# Sound_pollution.net
KiCad netlist of a schematic drawn in EAGLE
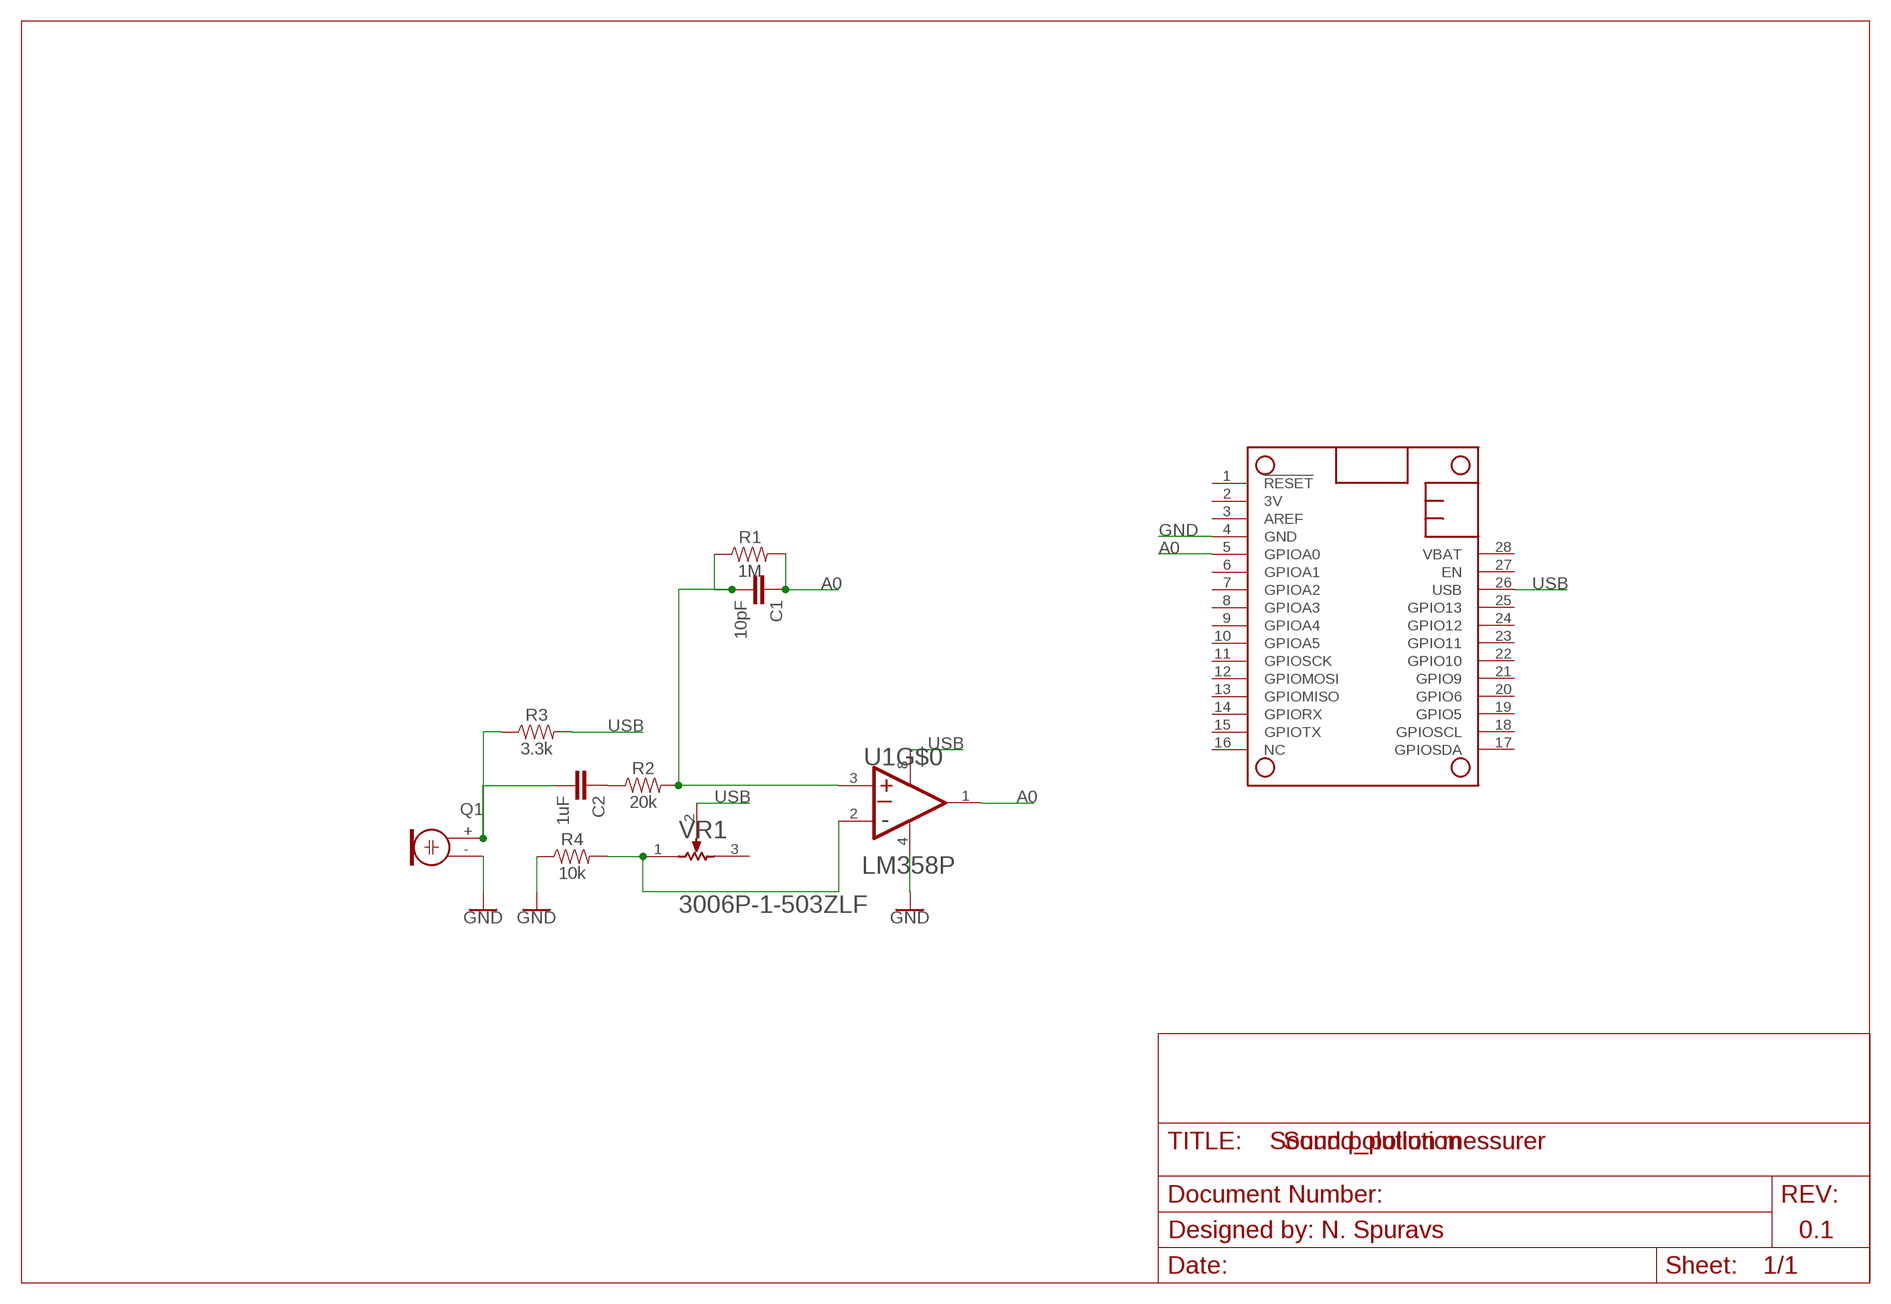
[diagram p0: schematic, sheet 1]

(export (version "E")
  (design (tool "Eeschema 10.0.6"))
  (components
    (comp (ref "C1")
      (value "10pF")
      (footprint "eagle-import:CAP-PTH-10MM")
      (libsource (lib "eagle-import") (part "10NF-PTH-10MM-10000V-1-%"))
    )
    (comp (ref "C2")
      (value "1uF")
      (footprint "eagle-import:CAP-PTH-10MM")
      (libsource (lib "eagle-import") (part "10NF-PTH-10MM-10000V-1-%"))
    )
    (comp (ref "MS1")
      (value "FEATHERWING")
      (footprint "eagle-import:FEATHERWING")
      (libsource (lib "eagle-import") (part "FEATHERWING"))
    )
    (comp (ref "Q1")
      (value "ELECTRET")
      (footprint "eagle-import:9.7ELECTRET")
      (libsource (lib "eagle-import") (part "ELECTRET"))
    )
    (comp (ref "R1")
      (value "1M")
      (footprint "eagle-import:AXIAL-0.3")
      (libsource (lib "eagle-import") (part "1KOHM-HORIZ-1/4W-1%"))
    )
    (comp (ref "R2")
      (value "20k")
      (footprint "eagle-import:AXIAL-0.3")
      (libsource (lib "eagle-import") (part "1KOHM-HORIZ-1/4W-1%"))
    )
    (comp (ref "R3")
      (value "3.3k")
      (footprint "eagle-import:AXIAL-0.3")
      (libsource (lib "eagle-import") (part "1KOHM-HORIZ-1/4W-1%"))
    )
    (comp (ref "R4")
      (value "10k")
      (footprint "eagle-import:AXIAL-0.3")
      (libsource (lib "eagle-import") (part "1KOHM-HORIZ-1/4W-1%"))
    )
    (comp (ref "U1")
      (value "TEXAS_INSTRUMENTS_LM358PTEXAS_INSTRUMENTS_LM358P_0_0")
      (footprint "eagle-import:TEXAS_INSTRUMENTS_LM358P_0")
      (fields
        (field (name "DIGIKEY_PART_NUMBER") "296-1395-5-ND")
        (field (name "MF") "Texas Instruments")
        (field (name "MOUSER_PART_NUMBER") "595-LM358P")
      )
      (libsource (lib "eagle-import") (part "TEXAS_INSTRUMENTS_LM358PTEXAS_INSTRUMENTS_LM358P_0_0"))
    )
    (comp (ref "VR1")
      (value "BOURNS_3006P-1-503ZLFBOURNS_3006P-1-503ZLF_0_0")
      (footprint "eagle-import:BOURNS_3006P-1-503ZLF_0")
      (fields (field (name "MF") "Bourns") (field (name "MPN") "3006P-1-503ZLF"))
      (libsource (lib "eagle-import") (part "BOURNS_3006P-1-503ZLFBOURNS_3006P-1-503ZLF_0_0"))
    )
  )
  (nets
    (net (code "1") (name "/3V") (class "Default")
      (node (ref "MS1") (pin "2") (pinfunction "3V_2") (pintype "power_in"))
    )
    (net (code "2") (name "/A0") (class "Default")
      (node (ref "C1") (pin "1") (pinfunction "1_1") (pintype "passive"))
      (node (ref "MS1") (pin "5") (pinfunction "GPIOA0_5") (pintype "bidirectional"))
      (node (ref "R1") (pin "P$2") (pinfunction "2_P$2") (pintype "passive"))
      (node (ref "U1") (pin "1") (pinfunction "1OUT_1") (pintype "output"))
    )
    (net (code "3") (name "/USB") (class "Default")
      (node (ref "MS1") (pin "26") (pinfunction "USB_26") (pintype "power_in"))
      (node (ref "R3") (pin "P$2") (pinfunction "2_P$2") (pintype "passive"))
      (node (ref "U1") (pin "8") (pinfunction "VCC_8") (pintype "power_in"))
      (node (ref "VR1") (pin "2") (pinfunction "WIPER_2") (pintype "passive"))
    )
    (net (code "4") (name "/VBAT") (class "Default")
      (node (ref "MS1") (pin "28") (pinfunction "VBAT_28") (pintype "power_in"))
    )
    (net (code "5") (name "GND") (class "Default")
      (node (ref "MS1") (pin "4") (pinfunction "GND_4") (pintype "power_in"))
      (node (ref "Q1") (pin "-") (pinfunction "1_-") (pintype "passive"))
      (node (ref "R4") (pin "P$1") (pinfunction "1_P$1") (pintype "passive"))
      (node (ref "U1") (pin "4") (pinfunction "GND_4") (pintype "power_in"))
    )
    (net (code "6") (name "Net-(Q1-2)") (class "Default")
      (node (ref "C2") (pin "2") (pinfunction "2_2") (pintype "passive"))
      (node (ref "Q1") (pin "+") (pinfunction "2_+") (pintype "passive"))
      (node (ref "R3") (pin "P$1") (pinfunction "1_P$1") (pintype "passive"))
    )
    (net (code "7") (name "Net-(R1-1)") (class "Default")
      (node (ref "C1") (pin "2") (pinfunction "2_2") (pintype "passive"))
      (node (ref "R1") (pin "P$1") (pinfunction "1_P$1") (pintype "passive"))
      (node (ref "R2") (pin "P$2") (pinfunction "2_P$2") (pintype "passive"))
      (node (ref "U1") (pin "3") (pinfunction "1IN+_3") (pintype "input"))
    )
    (net (code "8") (name "Net-(R2-1)") (class "Default")
      (node (ref "C2") (pin "1") (pinfunction "1_1") (pintype "passive"))
      (node (ref "R2") (pin "P$1") (pinfunction "1_P$1") (pintype "passive"))
    )
    (net (code "9") (name "Net-(R4-2)") (class "Default")
      (node (ref "R4") (pin "P$2") (pinfunction "2_P$2") (pintype "passive"))
      (node (ref "U1") (pin "2") (pinfunction "1IN-_2") (pintype "input"))
      (node (ref "VR1") (pin "1") (pinfunction "CCW_1") (pintype "passive"))
    )
    (net (code "10") (name "unconnected-(MS1-AREF-Pad3)") (class "Default")
      (node (ref "MS1") (pin "3") (pinfunction "AREF_3") (pintype "passive"))
    )
    (net (code "11") (name "unconnected-(MS1-EN-Pad27)") (class "Default")
      (node (ref "MS1") (pin "27") (pinfunction "EN_27") (pintype "passive"))
    )
    (net (code "12") (name "unconnected-(MS1-GPIO5-Pad19)") (class "Default")
      (node (ref "MS1") (pin "19") (pinfunction "GPIO5_19") (pintype "bidirectional"))
    )
    (net (code "13") (name "unconnected-(MS1-GPIO6-Pad20)") (class "Default")
      (node (ref "MS1") (pin "20") (pinfunction "GPIO6_20") (pintype "bidirectional"))
    )
    (net (code "14") (name "unconnected-(MS1-GPIO9-Pad21)") (class "Default")
      (node (ref "MS1") (pin "21") (pinfunction "GPIO9_21") (pintype "bidirectional"))
    )
    (net (code "15") (name "unconnected-(MS1-GPIO10-Pad22)") (class "Default")
      (node (ref "MS1") (pin "22") (pinfunction "GPIO10_22") (pintype "bidirectional"))
    )
    (net (code "16") (name "unconnected-(MS1-GPIO11-Pad23)") (class "Default")
      (node (ref "MS1") (pin "23") (pinfunction "GPIO11_23") (pintype "bidirectional"))
    )
    (net (code "17") (name "unconnected-(MS1-GPIO12-Pad24)") (class "Default")
      (node (ref "MS1") (pin "24") (pinfunction "GPIO12_24") (pintype "bidirectional"))
    )
    (net (code "18") (name "unconnected-(MS1-GPIO13-Pad25)") (class "Default")
      (node (ref "MS1") (pin "25") (pinfunction "GPIO13_25") (pintype "bidirectional"))
    )
    (net (code "19") (name "unconnected-(MS1-GPIOA1-Pad6)") (class "Default")
      (node (ref "MS1") (pin "6") (pinfunction "GPIOA1_6") (pintype "bidirectional"))
    )
    (net (code "20") (name "unconnected-(MS1-GPIOA2-Pad7)") (class "Default")
      (node (ref "MS1") (pin "7") (pinfunction "GPIOA2_7") (pintype "bidirectional"))
    )
    (net (code "21") (name "unconnected-(MS1-GPIOA3-Pad8)") (class "Default")
      (node (ref "MS1") (pin "8") (pinfunction "GPIOA3_8") (pintype "bidirectional"))
    )
    (net (code "22") (name "unconnected-(MS1-GPIOA4-Pad9)") (class "Default")
      (node (ref "MS1") (pin "9") (pinfunction "GPIOA4_9") (pintype "bidirectional"))
    )
    (net (code "23") (name "unconnected-(MS1-GPIOA5-Pad10)") (class "Default")
      (node (ref "MS1") (pin "10") (pinfunction "GPIOA5_10") (pintype "bidirectional"))
    )
    (net (code "24") (name "unconnected-(MS1-GPIOMISO-Pad13)") (class "Default")
      (node (ref "MS1") (pin "13") (pinfunction "GPIOMISO_13") (pintype "bidirectional"))
    )
    (net (code "25") (name "unconnected-(MS1-GPIOMOSI-Pad12)") (class "Default")
      (node (ref "MS1") (pin "12") (pinfunction "GPIOMOSI_12") (pintype "bidirectional"))
    )
    (net (code "26") (name "unconnected-(MS1-GPIORX-Pad14)") (class "Default")
      (node (ref "MS1") (pin "14") (pinfunction "GPIORX_14") (pintype "bidirectional"))
    )
    (net (code "27") (name "unconnected-(MS1-GPIOSCK-Pad11)") (class "Default")
      (node (ref "MS1") (pin "11") (pinfunction "GPIOSCK_11") (pintype "bidirectional"))
    )
    (net (code "28") (name "unconnected-(MS1-GPIOSCL-Pad18)") (class "Default")
      (node (ref "MS1") (pin "18") (pinfunction "GPIOSCL_18") (pintype "bidirectional"))
    )
    (net (code "29") (name "unconnected-(MS1-GPIOSDA-Pad17)") (class "Default")
      (node (ref "MS1") (pin "17") (pinfunction "GPIOSDA_17") (pintype "bidirectional"))
    )
    (net (code "30") (name "unconnected-(MS1-GPIOTX-Pad15)") (class "Default")
      (node (ref "MS1") (pin "15") (pinfunction "GPIOTX_15") (pintype "bidirectional"))
    )
    (net (code "31") (name "unconnected-(MS1-NC-Pad16)") (class "Default")
      (node (ref "MS1") (pin "16") (pinfunction "NC_16") (pintype "passive"))
    )
    (net (code "32") (name "unconnected-(MS1-~{RESET}-Pad1)") (class "Default")
      (node (ref "MS1") (pin "1") (pinfunction "~{RESET}_1") (pintype "input"))
    )
    (net (code "33") (name "unconnected-(VR1-CW-Pad3)") (class "Default")
      (node (ref "VR1") (pin "3") (pinfunction "CW_3") (pintype "passive"))
    )
  )
)
